# SpeechAnalyserV3.net
KiCad netlist of a schematic drawn in EAGLE
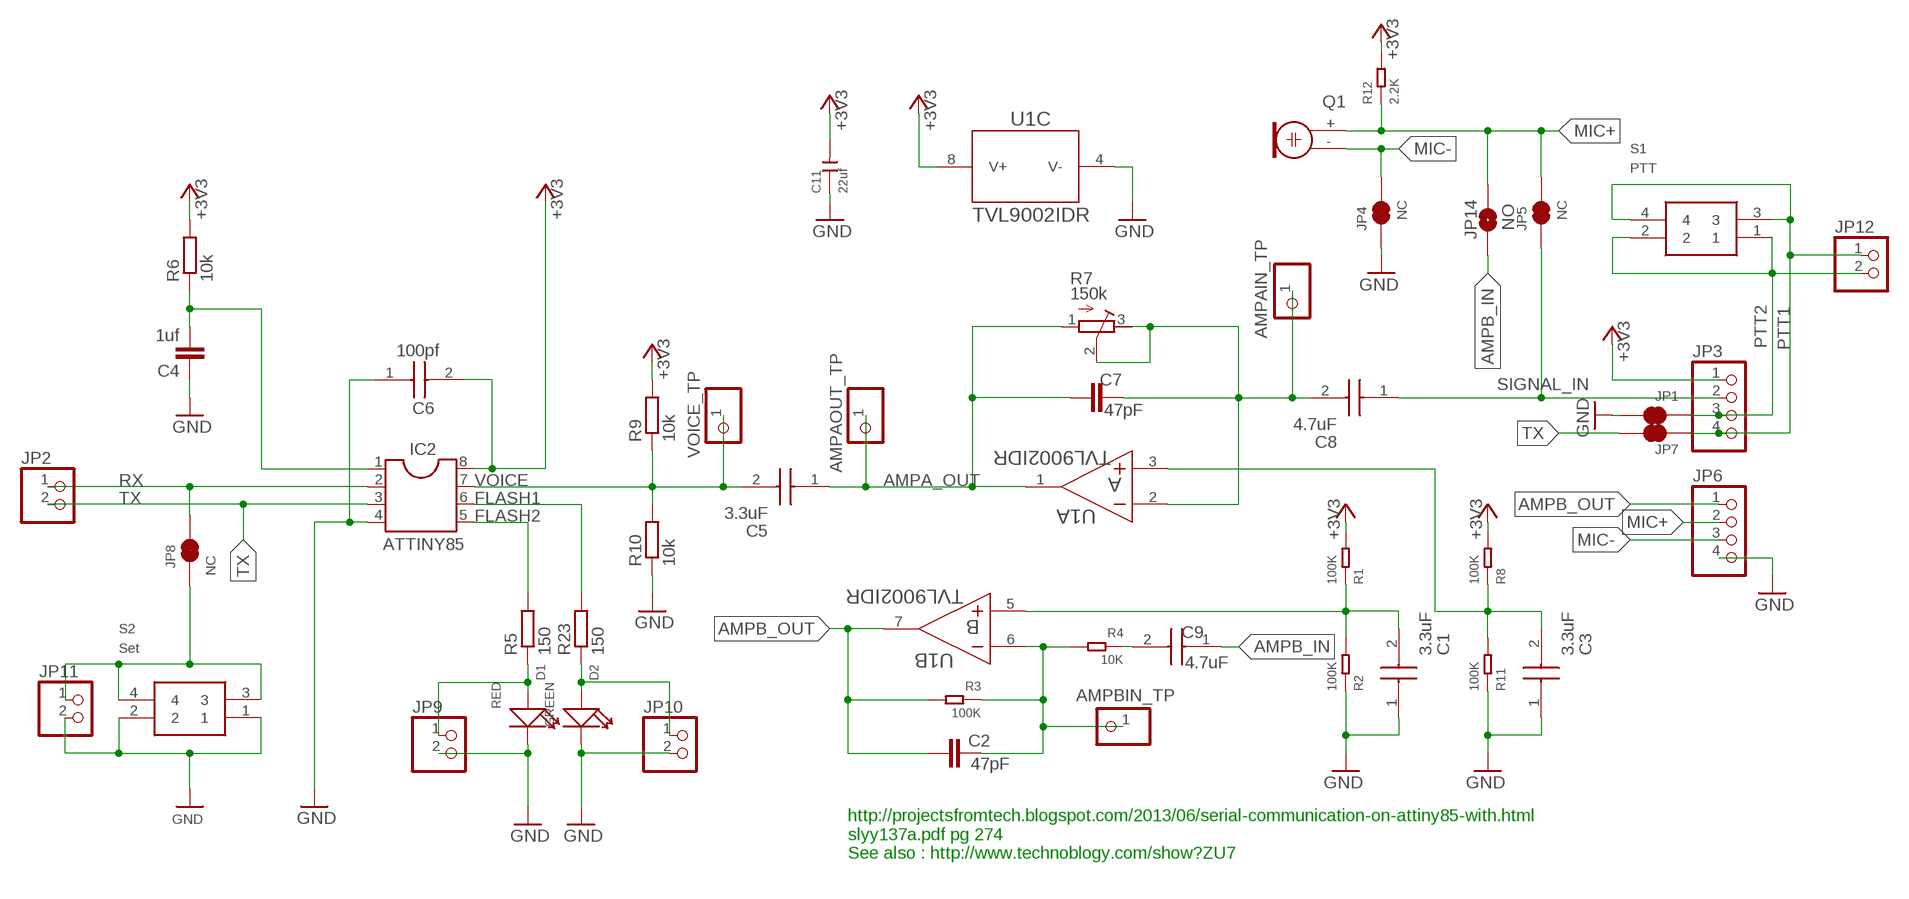
[diagram p0: schematic, sheet 1]

(export (version "E")
  (design (tool "Eeschema 10.0.6"))
  (components
    (comp (ref "AMPA_IN")
      (value "AMPAIN_TP")
      (footprint "eagle-import:1X01")
      (libsource (lib "eagle-import") (part "PINHD-1X1"))
    )
    (comp (ref "AMPA_OUT")
      (value "AMPAOUT_TP")
      (footprint "eagle-import:1X01")
      (libsource (lib "eagle-import") (part "PINHD-1X1"))
    )
    (comp (ref "AMPB_IN")
      (value "AMPBIN_TP")
      (footprint "eagle-import:1X01")
      (libsource (lib "eagle-import") (part "PINHD-1X1"))
    )
    (comp (ref "C1")
      (value "3.3uF")
      (footprint "eagle-import:CAPC2013X140N")
      (fields
        (field (name "MANUFACTURER_PART_NUMBER") "C0805C105K3RACTU")
        (field (name "MOUSER_PART_NUMBER") "80-C0805C105K3R")
      )
      (libsource (lib "eagle-import") (part "C0805C105K3RACTU"))
    )
    (comp (ref "C2")
      (value "47pF")
      (footprint "eagle-import:C0805")
      (libsource (lib "eagle-import") (part "C-EUC0805"))
    )
    (comp (ref "C3")
      (value "3.3uF")
      (footprint "eagle-import:CAPC2013X140N")
      (fields
        (field (name "MANUFACTURER_PART_NUMBER") "C0805C105K3RACTU")
        (field (name "MOUSER_PART_NUMBER") "80-C0805C105K3R")
      )
      (libsource (lib "eagle-import") (part "C0805C105K3RACTU"))
    )
    (comp (ref "C4")
      (value "1uf")
      (footprint "eagle-import:C0805")
      (libsource (lib "eagle-import") (part "C-EUC0805"))
    )
    (comp (ref "C5")
      (value "3.3uF")
      (footprint "eagle-import:CAPC2013X140N")
      (fields
        (field (name "MANUFACTURER_PART_NUMBER") "C0805C105K3RACTU")
        (field (name "MOUSER_PART_NUMBER") "80-C0805C105K3R")
      )
      (libsource (lib "eagle-import") (part "C0805C105K3RACTU"))
    )
    (comp (ref "C6")
      (value "100pf")
      (footprint "eagle-import:CAPC2012X90N")
      (fields (field (name "MANUFACTURER_PART_NUMBER") "885012207080") (field (name "DISPLAY_VALUE") "100pf"))
      (libsource (lib "eagle-import") (part "885012207080"))
    )
    (comp (ref "C7")
      (value "47pF")
      (footprint "eagle-import:C0805")
      (libsource (lib "eagle-import") (part "C-EUC0805"))
    )
    (comp (ref "C8")
      (value "4.7uF")
      (footprint "eagle-import:CAPC2013X140N")
      (fields
        (field (name "MANUFACTURER_PART_NUMBER") "C0805C105K3RACTU")
        (field (name "MOUSER_PART_NUMBER") "80-C0805C105K3R")
      )
      (libsource (lib "eagle-import") (part "C0805C105K3RACTU"))
    )
    (comp (ref "C9")
      (value "4.7uF")
      (footprint "eagle-import:CAPC2013X140N")
      (fields
        (field (name "MANUFACTURER_PART_NUMBER") "C0805C105K3RACTU")
        (field (name "MOUSER_PART_NUMBER") "80-C0805C105K3R")
      )
      (libsource (lib "eagle-import") (part "C0805C105K3RACTU"))
    )
    (comp (ref "C11")
      (value "22uf")
      (footprint "eagle-import:C1206")
      (libsource (lib "eagle-import") (part "CERAMIC-22UF-16V-10%-X7R(1206)"))
    )
    (comp (ref "D1")
      (value "RED")
      (footprint "eagle-import:LED-0805")
      (fields (field (name "MPN") "17-215SURC/S530-A2/TR8"))
      (libsource (lib "eagle-import") (part "SMD-LED-CLEAR-RED(0805)"))
    )
    (comp (ref "D2")
      (value "GREEN")
      (footprint "eagle-import:LED-0805")
      (fields (field (name "MPN") "17-215SYGC/S530-E2/TR8"))
      (libsource (lib "eagle-import") (part "SMD-LED-CLEAR-GREEN(0805)"))
    )
    (comp (ref "IC2")
      (value "ATTINY85")
      (footprint "eagle-import:SOCKET-08")
      (libsource (lib "eagle-import") (part "DIL8S"))
    )
    (comp (ref "JP1")
      (value "NC")
      (footprint "eagle-import:SMT-JUMPER_2_NC_TRACE_SILK")
      (libsource (lib "eagle-import") (part "JUMPER-SMT_2_NC_TRACE_SILK"))
    )
    (comp (ref "JP2")
      (value "PINHD-1X2")
      (footprint "eagle-import:1X02")
      (libsource (lib "eagle-import") (part "PINHD-1X2"))
    )
    (comp (ref "JP3")
      (value "PINHD-1X4")
      (footprint "eagle-import:1X04")
      (libsource (lib "eagle-import") (part "PINHD-1X4"))
    )
    (comp (ref "JP4")
      (value "NC")
      (footprint "eagle-import:SMT-JUMPER_2_NC_TRACE_SILK")
      (libsource (lib "eagle-import") (part "JUMPER-SMT_2_NC_TRACE_SILK"))
    )
    (comp (ref "JP5")
      (value "NC")
      (footprint "eagle-import:SMT-JUMPER_2_NC_TRACE_SILK")
      (libsource (lib "eagle-import") (part "JUMPER-SMT_2_NC_TRACE_SILK"))
    )
    (comp (ref "JP6")
      (value "PINHD-1X4")
      (footprint "eagle-import:1X04")
      (libsource (lib "eagle-import") (part "PINHD-1X4"))
    )
    (comp (ref "JP7")
      (value "NC")
      (footprint "eagle-import:SMT-JUMPER_2_NC_TRACE_SILK")
      (libsource (lib "eagle-import") (part "JUMPER-SMT_2_NC_TRACE_SILK"))
    )
    (comp (ref "JP8")
      (value "NC")
      (footprint "eagle-import:SMT-JUMPER_2_NC_TRACE_SILK")
      (libsource (lib "eagle-import") (part "JUMPER-SMT_2_NC_TRACE_SILK"))
    )
    (comp (ref "JP9")
      (value "PINHD-1X2")
      (footprint "eagle-import:1X02")
      (libsource (lib "eagle-import") (part "PINHD-1X2"))
    )
    (comp (ref "JP10")
      (value "PINHD-1X2")
      (footprint "eagle-import:1X02")
      (libsource (lib "eagle-import") (part "PINHD-1X2"))
    )
    (comp (ref "JP11")
      (value "PINHD-1X2")
      (footprint "eagle-import:1X02")
      (libsource (lib "eagle-import") (part "PINHD-1X2"))
    )
    (comp (ref "JP12")
      (value "PINHD-1X2")
      (footprint "eagle-import:1X02")
      (libsource (lib "eagle-import") (part "PINHD-1X2"))
    )
    (comp (ref "JP14")
      (value "NO")
      (footprint "eagle-import:SMT-JUMPER_2_NO_SILK")
      (libsource (lib "eagle-import") (part "JUMPER-SMT_2_NO_SILK"))
    )
    (comp (ref "Q1")
      (value "ELECTRET")
      (footprint "eagle-import:9.7ELECTRET")
      (libsource (lib "eagle-import") (part "ELECTRET"))
    )
    (comp (ref "R1")
      (value "100K")
      (footprint "eagle-import:R0805")
      (fields (field (name "MPN") "RC0805JR-07100RL"))
      (libsource (lib "eagle-import") (part "SMD-RES-100R-5%-1/8W(0805)"))
    )
    (comp (ref "R2")
      (value "100K")
      (footprint "eagle-import:R0805")
      (fields (field (name "MPN") "RC0805JR-07100RL"))
      (libsource (lib "eagle-import") (part "SMD-RES-100R-5%-1/8W(0805)"))
    )
    (comp (ref "R3")
      (value "100K")
      (footprint "eagle-import:R0805")
      (fields (field (name "MPN") "RC0805JR-07100RL"))
      (libsource (lib "eagle-import") (part "SMD-RES-100R-5%-1/8W(0805)"))
    )
    (comp (ref "R4")
      (value "10K")
      (footprint "eagle-import:R0805")
      (fields (field (name "MPN") "RC0805JR-07100RL"))
      (libsource (lib "eagle-import") (part "SMD-RES-100R-5%-1/8W(0805)"))
    )
    (comp (ref "R5")
      (value "150")
      (footprint "eagle-import:R0805")
      (libsource (lib "eagle-import") (part "R-EU_R0805"))
    )
    (comp (ref "R6")
      (value "10k")
      (footprint "eagle-import:R0805")
      (libsource (lib "eagle-import") (part "R-EU_R0805"))
    )
    (comp (ref "R7")
      (value "150k")
      (footprint "eagle-import:RTRIM64W")
      (libsource (lib "eagle-import") (part "R-TRIMM64W"))
    )
    (comp (ref "R8")
      (value "100K")
      (footprint "eagle-import:R0805")
      (fields (field (name "MPN") "RC0805JR-07100RL"))
      (libsource (lib "eagle-import") (part "SMD-RES-100R-5%-1/8W(0805)"))
    )
    (comp (ref "R9")
      (value "10k")
      (footprint "eagle-import:R0805")
      (libsource (lib "eagle-import") (part "R-EU_R0805"))
    )
    (comp (ref "R10")
      (value "10k")
      (footprint "eagle-import:R0805")
      (libsource (lib "eagle-import") (part "R-EU_R0805"))
    )
    (comp (ref "R11")
      (value "100K")
      (footprint "eagle-import:R0805")
      (fields (field (name "MPN") "RC0805JR-07100RL"))
      (libsource (lib "eagle-import") (part "SMD-RES-100R-5%-1/8W(0805)"))
    )
    (comp (ref "R12")
      (value "2.2K")
      (footprint "eagle-import:R0805")
      (fields (field (name "MPN") "RC0805JR-072K2L"))
      (libsource (lib "eagle-import") (part "SMD-RES-2.2K-5%-1/8W(0805)"))
    )
    (comp (ref "R23")
      (value "150")
      (footprint "eagle-import:R0805")
      (libsource (lib "eagle-import") (part "R-EU_R0805"))
    )
    (comp (ref "S1")
      (value "PTT")
      (footprint "eagle-import:B3FS-1000P")
      (fields
        (field (name "MANUFACTURER_PART_NUMBER") "B3FS-1000P")
        (field (name "MOUSER_PART_NUMBER") "653-B3FS-1000P")
      )
      (libsource (lib "eagle-import") (part "B3FS-1000P"))
    )
    (comp (ref "S2")
      (value "Set")
      (footprint "eagle-import:B3FS-1000P")
      (fields
        (field (name "MANUFACTURER_PART_NUMBER") "B3FS-1000P")
        (field (name "MOUSER_PART_NUMBER") "653-B3FS-1000P")
      )
      (libsource (lib "eagle-import") (part "B3FS-1000P"))
    )
    (comp (ref "U1")
      (value "TVL9002IDR")
      (footprint "eagle-import:D0008A_N")
      (fields (field (name "MANUFACTURER") "Texas Instruments") (field (name "PARTNUMBER") "TLV9002IDR"))
      (libsource (lib "eagle-import") (part "TLV9002IDR"))
    )
    (comp (ref "VOICE")
      (value "VOICE_TP")
      (footprint "eagle-import:1X01")
      (libsource (lib "eagle-import") (part "PINHD-1X1"))
    )
  )
  (nets
    (net (code "1") (name "+3V3") (class "Default")
      (node (ref "C11") (pin "2") (pinfunction "2_2") (pintype "passive"))
      (node (ref "C6") (pin "2") (pinfunction "2_2") (pintype "bidirectional"))
      (node (ref "IC2") (pin "8") (pinfunction "8_8") (pintype "passive"))
      (node (ref "JP3") (pin "1") (pinfunction "1_1") (pintype "passive"))
      (node (ref "R1") (pin "2") (pinfunction "2_2") (pintype "passive"))
      (node (ref "R12") (pin "2") (pinfunction "2_2") (pintype "passive"))
      (node (ref "R6") (pin "2") (pinfunction "2_2") (pintype "passive"))
      (node (ref "R8") (pin "2") (pinfunction "2_2") (pintype "passive"))
      (node (ref "R9") (pin "2") (pinfunction "2_2") (pintype "passive"))
      (node (ref "U1") (pin "8") (pinfunction "V+_8") (pintype "power_in"))
    )
    (net (code "2") (name "/AMPA_OUT") (class "Default")
      (node (ref "AMPA_OUT") (pin "1") (pinfunction "1_1") (pintype "passive"))
      (node (ref "C5") (pin "1") (pinfunction "C1_1") (pintype "bidirectional"))
      (node (ref "C7") (pin "1") (pinfunction "1_1") (pintype "passive"))
      (node (ref "R7") (pin "1") (pinfunction "A_1") (pintype "passive"))
      (node (ref "U1") (pin "1") (pinfunction "OUT_1") (pintype "output"))
    )
    (net (code "3") (name "/FLASH1") (class "Default")
      (node (ref "IC2") (pin "6") (pinfunction "6_6") (pintype "passive"))
      (node (ref "R23") (pin "2") (pinfunction "2_2") (pintype "passive"))
    )
    (net (code "4") (name "/FLASH2") (class "Default")
      (node (ref "IC2") (pin "5") (pinfunction "5_5") (pintype "passive"))
      (node (ref "R5") (pin "2") (pinfunction "2_2") (pintype "passive"))
    )
    (net (code "5") (name "/PTT1") (class "Default")
      (node (ref "JP12") (pin "1") (pinfunction "1_1") (pintype "passive"))
      (node (ref "JP3") (pin "4") (pinfunction "4_4") (pintype "passive"))
      (node (ref "JP7") (pin "2") (pinfunction "2_2") (pintype "passive"))
      (node (ref "S1") (pin "3") (pinfunction "3_3") (pintype "bidirectional"))
      (node (ref "S1") (pin "4") (pinfunction "4_4") (pintype "bidirectional"))
    )
    (net (code "6") (name "/PTT2") (class "Default")
      (node (ref "JP1") (pin "2") (pinfunction "2_2") (pintype "passive"))
      (node (ref "JP12") (pin "2") (pinfunction "2_2") (pintype "passive"))
      (node (ref "JP3") (pin "3") (pinfunction "3_3") (pintype "passive"))
      (node (ref "S1") (pin "1") (pinfunction "1_1") (pintype "bidirectional"))
      (node (ref "S1") (pin "2") (pinfunction "2_2") (pintype "bidirectional"))
    )
    (net (code "7") (name "/RX") (class "Default")
      (node (ref "IC2") (pin "2") (pinfunction "2_2") (pintype "passive"))
      (node (ref "JP2") (pin "1") (pinfunction "1_1") (pintype "passive"))
      (node (ref "JP8") (pin "2") (pinfunction "2_2") (pintype "passive"))
    )
    (net (code "8") (name "/SIGNAL_IN") (class "Default")
      (node (ref "C8") (pin "1") (pinfunction "C1_1") (pintype "bidirectional"))
      (node (ref "JP3") (pin "2") (pinfunction "2_2") (pintype "passive"))
      (node (ref "JP5") (pin "1") (pinfunction "1_1") (pintype "passive"))
    )
    (net (code "9") (name "/VOICE") (class "Default")
      (node (ref "C5") (pin "2") (pinfunction "C2_2") (pintype "bidirectional"))
      (node (ref "IC2") (pin "7") (pinfunction "7_7") (pintype "passive"))
      (node (ref "R10") (pin "2") (pinfunction "2_2") (pintype "passive"))
      (node (ref "R9") (pin "1") (pinfunction "1_1") (pintype "passive"))
      (node (ref "VOICE") (pin "1") (pinfunction "1_1") (pintype "passive"))
    )
    (net (code "10") (name "AMPB_IN") (class "Default")
      (node (ref "C9") (pin "1") (pinfunction "C1_1") (pintype "bidirectional"))
      (node (ref "JP14") (pin "1") (pinfunction "1_1") (pintype "passive"))
    )
    (net (code "11") (name "AMPB_OUT") (class "Default")
      (node (ref "C2") (pin "1") (pinfunction "1_1") (pintype "passive"))
      (node (ref "JP6") (pin "1") (pinfunction "1_1") (pintype "passive"))
      (node (ref "R3") (pin "2") (pinfunction "2_2") (pintype "passive"))
      (node (ref "U1") (pin "7") (pinfunction "OUT_7") (pintype "output"))
    )
    (net (code "12") (name "GND") (class "Default")
      (node (ref "C1") (pin "1") (pinfunction "C1_1") (pintype "bidirectional"))
      (node (ref "C11") (pin "1") (pinfunction "1_1") (pintype "passive"))
      (node (ref "C3") (pin "1") (pinfunction "C1_1") (pintype "bidirectional"))
      (node (ref "C4") (pin "1") (pinfunction "1_1") (pintype "passive"))
      (node (ref "C6") (pin "1") (pinfunction "1_1") (pintype "bidirectional"))
      (node (ref "D1") (pin "-") (pinfunction "-_-") (pintype "passive"))
      (node (ref "D2") (pin "-") (pinfunction "-_-") (pintype "passive"))
      (node (ref "IC2") (pin "4") (pinfunction "4_4") (pintype "passive"))
      (node (ref "JP1") (pin "1") (pinfunction "1_1") (pintype "passive"))
      (node (ref "JP10") (pin "2") (pinfunction "2_2") (pintype "passive"))
      (node (ref "JP11") (pin "2") (pinfunction "2_2") (pintype "passive"))
      (node (ref "JP4") (pin "1") (pinfunction "1_1") (pintype "passive"))
      (node (ref "JP6") (pin "4") (pinfunction "4_4") (pintype "passive"))
      (node (ref "JP9") (pin "2") (pinfunction "2_2") (pintype "passive"))
      (node (ref "R10") (pin "1") (pinfunction "1_1") (pintype "passive"))
      (node (ref "R11") (pin "1") (pinfunction "1_1") (pintype "passive"))
      (node (ref "R2") (pin "1") (pinfunction "1_1") (pintype "passive"))
      (node (ref "S2") (pin "1") (pinfunction "1_1") (pintype "bidirectional"))
      (node (ref "S2") (pin "2") (pinfunction "2_2") (pintype "bidirectional"))
      (node (ref "U1") (pin "4") (pinfunction "V-_4") (pintype "power_in"))
    )
    (net (code "13") (name "MIC+") (class "Default")
      (node (ref "JP14") (pin "2") (pinfunction "2_2") (pintype "passive"))
      (node (ref "JP5") (pin "2") (pinfunction "2_2") (pintype "passive"))
      (node (ref "JP6") (pin "2") (pinfunction "2_2") (pintype "passive"))
      (node (ref "Q1") (pin "+") (pinfunction "2_+") (pintype "passive"))
      (node (ref "R12") (pin "1") (pinfunction "1_1") (pintype "passive"))
    )
    (net (code "14") (name "MIC-") (class "Default")
      (node (ref "JP4") (pin "2") (pinfunction "2_2") (pintype "passive"))
      (node (ref "JP6") (pin "3") (pinfunction "3_3") (pintype "passive"))
      (node (ref "Q1") (pin "-") (pinfunction "1_-") (pintype "passive"))
    )
    (net (code "15") (name "Net-(C1-C2)") (class "Default")
      (node (ref "C1") (pin "2") (pinfunction "C2_2") (pintype "bidirectional"))
      (node (ref "R1") (pin "1") (pinfunction "1_1") (pintype "passive"))
      (node (ref "R2") (pin "2") (pinfunction "2_2") (pintype "passive"))
      (node (ref "U1") (pin "5") (pinfunction "IN+_5") (pintype "input"))
    )
    (net (code "16") (name "Net-(C3-C2)") (class "Default")
      (node (ref "C3") (pin "2") (pinfunction "C2_2") (pintype "bidirectional"))
      (node (ref "R11") (pin "2") (pinfunction "2_2") (pintype "passive"))
      (node (ref "R8") (pin "1") (pinfunction "1_1") (pintype "passive"))
      (node (ref "U1") (pin "3") (pinfunction "IN+_3") (pintype "input"))
    )
    (net (code "17") (name "Net-(C4-Pad2)") (class "Default")
      (node (ref "C4") (pin "2") (pinfunction "2_2") (pintype "passive"))
      (node (ref "IC2") (pin "1") (pinfunction "1_1") (pintype "passive"))
      (node (ref "R6") (pin "1") (pinfunction "1_1") (pintype "passive"))
    )
    (net (code "18") (name "Net-(C8-C2)") (class "Default")
      (node (ref "AMPA_IN") (pin "1") (pinfunction "1_1") (pintype "passive"))
      (node (ref "C7") (pin "2") (pinfunction "2_2") (pintype "passive"))
      (node (ref "C8") (pin "2") (pinfunction "C2_2") (pintype "bidirectional"))
      (node (ref "R7") (pin "2") (pinfunction "S_2") (pintype "passive"))
      (node (ref "R7") (pin "3") (pinfunction "E_3") (pintype "passive"))
      (node (ref "U1") (pin "2") (pinfunction "IN-_2") (pintype "input"))
    )
    (net (code "19") (name "Net-(C9-C2)") (class "Default")
      (node (ref "C9") (pin "2") (pinfunction "C2_2") (pintype "bidirectional"))
      (node (ref "R4") (pin "1") (pinfunction "1_1") (pintype "passive"))
    )
    (net (code "20") (name "Net-(D1-Pad+)") (class "Default")
      (node (ref "D1") (pin "+") (pinfunction "+_+") (pintype "passive"))
      (node (ref "JP9") (pin "1") (pinfunction "1_1") (pintype "passive"))
      (node (ref "R5") (pin "1") (pinfunction "1_1") (pintype "passive"))
    )
    (net (code "21") (name "Net-(D2-Pad+)") (class "Default")
      (node (ref "D2") (pin "+") (pinfunction "+_+") (pintype "passive"))
      (node (ref "JP10") (pin "1") (pinfunction "1_1") (pintype "passive"))
      (node (ref "R23") (pin "1") (pinfunction "1_1") (pintype "passive"))
    )
    (net (code "22") (name "Net-(JP11-Pad1)") (class "Default")
      (node (ref "JP11") (pin "1") (pinfunction "1_1") (pintype "passive"))
      (node (ref "JP8") (pin "1") (pinfunction "1_1") (pintype "passive"))
      (node (ref "S2") (pin "3") (pinfunction "3_3") (pintype "bidirectional"))
      (node (ref "S2") (pin "4") (pinfunction "4_4") (pintype "bidirectional"))
    )
    (net (code "23") (name "Net-(U1B-IN-)") (class "Default")
      (node (ref "AMPB_IN") (pin "1") (pinfunction "1_1") (pintype "passive"))
      (node (ref "C2") (pin "2") (pinfunction "2_2") (pintype "passive"))
      (node (ref "R3") (pin "1") (pinfunction "1_1") (pintype "passive"))
      (node (ref "R4") (pin "2") (pinfunction "2_2") (pintype "passive"))
      (node (ref "U1") (pin "6") (pinfunction "IN-_6") (pintype "input"))
    )
    (net (code "24") (name "TX") (class "Default")
      (node (ref "IC2") (pin "3") (pinfunction "3_3") (pintype "passive"))
      (node (ref "JP2") (pin "2") (pinfunction "2_2") (pintype "passive"))
      (node (ref "JP7") (pin "1") (pinfunction "1_1") (pintype "passive"))
    )
  )
)
